# PP3_ptC_Alim.net
KiCad netlist of a schematic drawn in Altium Designer
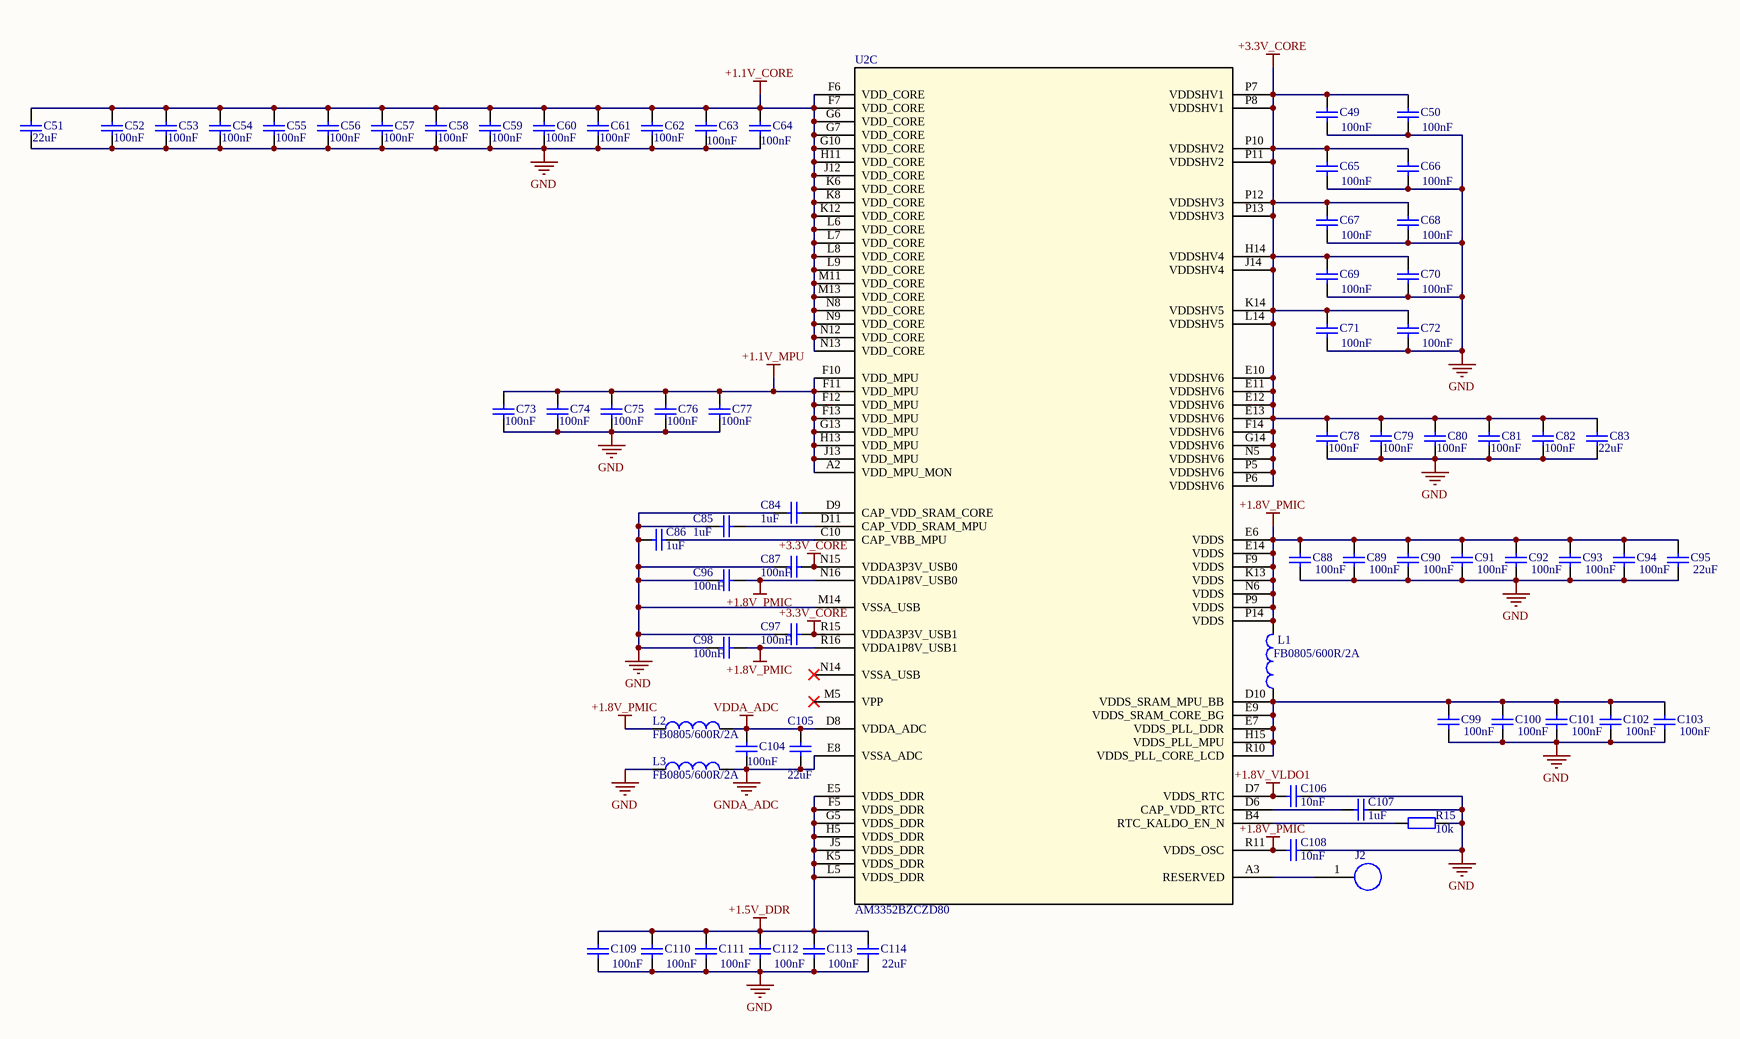
[diagram p0: PP3_ptC_Alim.SchDoc]

(export (version "E")
  (design (tool "Eeschema 10.0.6"))
  (components
    (comp (ref "C49")
      (value "100nF")
      (footprint "CAPC1005X05 (0402)")
      (description "Capacitor")
      (fields (field (name "Comment") "Cap 100nF"))
      (libsource (lib "Michel") (part "Cap"))
    )
    (comp (ref "C50")
      (value "100nF")
      (footprint "CAPC1005X05 (0402)")
      (description "Capacitor")
      (fields (field (name "Comment") "Cap 100nF"))
      (libsource (lib "Michel") (part "Cap"))
    )
    (comp (ref "C51")
      (value "22uF")
      (footprint "0805 (2012 metric)")
      (description "Capacitor")
      (fields (field (name "Comment") "Cap 22uF"))
      (libsource (lib "Michel") (part "Cap"))
    )
    (comp (ref "C52")
      (value "100nF")
      (footprint "CAPC1005X05 (0402)")
      (description "Capacitor")
      (fields (field (name "Comment") "Cap 100nF"))
      (libsource (lib "Michel") (part "Cap"))
    )
    (comp (ref "C53")
      (value "100nF")
      (footprint "CAPC1005X05 (0402)")
      (description "Capacitor")
      (fields (field (name "Comment") "Cap 100nF"))
      (libsource (lib "Michel") (part "Cap"))
    )
    (comp (ref "C54")
      (value "100nF")
      (footprint "CAPC1005X05 (0402)")
      (description "Capacitor")
      (fields (field (name "Comment") "Cap 100nF"))
      (libsource (lib "Michel") (part "Cap"))
    )
    (comp (ref "C55")
      (value "100nF")
      (footprint "CAPC1005X05 (0402)")
      (description "Capacitor")
      (fields (field (name "Comment") "Cap 100nF"))
      (libsource (lib "Michel") (part "Cap"))
    )
    (comp (ref "C56")
      (value "100nF")
      (footprint "CAPC1005X05 (0402)")
      (description "Capacitor")
      (fields (field (name "Comment") "Cap 100nF"))
      (libsource (lib "Michel") (part "Cap"))
    )
    (comp (ref "C57")
      (value "100nF")
      (footprint "CAPC1005X05 (0402)")
      (description "Capacitor")
      (fields (field (name "Comment") "Cap 100nF"))
      (libsource (lib "Michel") (part "Cap"))
    )
    (comp (ref "C58")
      (value "100nF")
      (footprint "CAPC1005X05 (0402)")
      (description "Capacitor")
      (fields (field (name "Comment") "Cap 100nF"))
      (libsource (lib "Michel") (part "Cap"))
    )
    (comp (ref "C59")
      (value "100nF")
      (footprint "CAPC1005X05 (0402)")
      (description "Capacitor")
      (fields (field (name "Comment") "Cap 100nF"))
      (libsource (lib "Michel") (part "Cap"))
    )
    (comp (ref "C60")
      (value "100nF")
      (footprint "CAPC1005X05 (0402)")
      (description "Capacitor")
      (fields (field (name "Comment") "Cap 100nF"))
      (libsource (lib "Michel") (part "Cap"))
    )
    (comp (ref "C61")
      (value "100nF")
      (footprint "CAPC1005X05 (0402)")
      (description "Capacitor")
      (fields (field (name "Comment") "Cap 100nF"))
      (libsource (lib "Michel") (part "Cap"))
    )
    (comp (ref "C62")
      (value "100nF")
      (footprint "CAPC1005X05 (0402)")
      (description "Capacitor")
      (fields (field (name "Comment") "Cap 100nF"))
      (libsource (lib "Michel") (part "Cap"))
    )
    (comp (ref "C63")
      (value "100nF")
      (footprint "CAPC1005X05 (0402)")
      (description "Capacitor")
      (fields (field (name "Comment") "Cap 100nF"))
      (libsource (lib "Michel") (part "Cap"))
    )
    (comp (ref "C64")
      (value "100nF")
      (footprint "CAPC1005X05 (0402)")
      (description "Capacitor")
      (fields (field (name "Comment") "Cap 100nF"))
      (libsource (lib "Michel") (part "Cap"))
    )
    (comp (ref "C65")
      (value "100nF")
      (footprint "CAPC1005X05 (0402)")
      (description "Capacitor")
      (fields (field (name "Comment") "Cap 100nF"))
      (libsource (lib "Michel") (part "Cap"))
    )
    (comp (ref "C66")
      (value "100nF")
      (footprint "CAPC1005X05 (0402)")
      (description "Capacitor")
      (fields (field (name "Comment") "Cap 100nF"))
      (libsource (lib "Michel") (part "Cap"))
    )
    (comp (ref "C67")
      (value "100nF")
      (footprint "CAPC1005X05 (0402)")
      (description "Capacitor")
      (fields (field (name "Comment") "Cap 100nF"))
      (libsource (lib "Michel") (part "Cap"))
    )
    (comp (ref "C68")
      (value "100nF")
      (footprint "CAPC1005X05 (0402)")
      (description "Capacitor")
      (fields (field (name "Comment") "Cap 100nF"))
      (libsource (lib "Michel") (part "Cap"))
    )
    (comp (ref "C69")
      (value "100nF")
      (footprint "CAPC1005X05 (0402)")
      (description "Capacitor")
      (fields (field (name "Comment") "Cap 100nF"))
      (libsource (lib "Michel") (part "Cap"))
    )
    (comp (ref "C70")
      (value "100nF")
      (footprint "CAPC1005X05 (0402)")
      (description "Capacitor")
      (fields (field (name "Comment") "Cap 100nF"))
      (libsource (lib "Michel") (part "Cap"))
    )
    (comp (ref "C71")
      (value "100nF")
      (footprint "CAPC1005X05 (0402)")
      (description "Capacitor")
      (fields (field (name "Comment") "Cap 100nF"))
      (libsource (lib "Michel") (part "Cap"))
    )
    (comp (ref "C72")
      (value "100nF")
      (footprint "CAPC1005X05 (0402)")
      (description "Capacitor")
      (fields (field (name "Comment") "Cap 100nF"))
      (libsource (lib "Michel") (part "Cap"))
    )
    (comp (ref "C73")
      (value "100nF")
      (footprint "CAPC1005X05 (0402)")
      (description "Capacitor")
      (fields (field (name "Comment") "Cap 100nF"))
      (libsource (lib "Michel") (part "Cap"))
    )
    (comp (ref "C74")
      (value "100nF")
      (footprint "CAPC1005X05 (0402)")
      (description "Capacitor")
      (fields (field (name "Comment") "Cap 100nF"))
      (libsource (lib "Michel") (part "Cap"))
    )
    (comp (ref "C75")
      (value "100nF")
      (footprint "CAPC1005X05 (0402)")
      (description "Capacitor")
      (fields (field (name "Comment") "Cap 100nF"))
      (libsource (lib "Michel") (part "Cap"))
    )
    (comp (ref "C76")
      (value "100nF")
      (footprint "CAPC1005X05 (0402)")
      (description "Capacitor")
      (fields (field (name "Comment") "Cap 100nF"))
      (libsource (lib "Michel") (part "Cap"))
    )
    (comp (ref "C77")
      (value "100nF")
      (footprint "CAPC1005X05 (0402)")
      (description "Capacitor")
      (fields (field (name "Comment") "Cap 100nF"))
      (libsource (lib "Michel") (part "Cap"))
    )
    (comp (ref "C78")
      (value "100nF")
      (footprint "CAPC1005X05 (0402)")
      (description "Capacitor")
      (fields (field (name "Comment") "Cap 100nF"))
      (libsource (lib "Michel") (part "Cap"))
    )
    (comp (ref "C79")
      (value "100nF")
      (footprint "CAPC1005X05 (0402)")
      (description "Capacitor")
      (fields (field (name "Comment") "Cap 100nF"))
      (libsource (lib "Michel") (part "Cap"))
    )
    (comp (ref "C80")
      (value "100nF")
      (footprint "CAPC1005X05 (0402)")
      (description "Capacitor")
      (fields (field (name "Comment") "Cap 100nF"))
      (libsource (lib "Michel") (part "Cap"))
    )
    (comp (ref "C81")
      (value "100nF")
      (footprint "CAPC1005X05 (0402)")
      (description "Capacitor")
      (fields (field (name "Comment") "Cap 100nF"))
      (libsource (lib "Michel") (part "Cap"))
    )
    (comp (ref "C82")
      (value "100nF")
      (footprint "CAPC1005X05 (0402)")
      (description "Capacitor")
      (fields (field (name "Comment") "Cap 100nF"))
      (libsource (lib "Michel") (part "Cap"))
    )
    (comp (ref "C83")
      (value "22uF")
      (footprint "0805 (2012 metric)")
      (description "Capacitor")
      (fields (field (name "Comment") "Cap 22uF"))
      (libsource (lib "Michel") (part "Cap"))
    )
    (comp (ref "C84")
      (value "1uF")
      (footprint "CAPC1608X08")
      (description "Capacitor")
      (fields (field (name "Comment") "Cap 1uF"))
      (libsource (lib "Michel") (part "Cap"))
    )
    (comp (ref "C85")
      (value "1uF")
      (footprint "CAPC1608X08")
      (description "Capacitor")
      (fields (field (name "Comment") "Cap 1uF"))
      (libsource (lib "Michel") (part "Cap"))
    )
    (comp (ref "C86")
      (value "1uF")
      (footprint "CAPC1608X08")
      (description "Capacitor")
      (fields (field (name "Comment") "Cap 1uF"))
      (libsource (lib "Michel") (part "Cap"))
    )
    (comp (ref "C87")
      (value "100nF")
      (footprint "CAPC1005X05 (0402)")
      (description "Capacitor")
      (fields (field (name "Comment") "Cap 100nF"))
      (libsource (lib "Michel") (part "Cap"))
    )
    (comp (ref "C88")
      (value "100nF")
      (footprint "CAPC1005X05 (0402)")
      (description "Capacitor")
      (fields (field (name "Comment") "Cap 100nF"))
      (libsource (lib "Michel") (part "Cap"))
    )
    (comp (ref "C89")
      (value "100nF")
      (footprint "CAPC1005X05 (0402)")
      (description "Capacitor")
      (fields (field (name "Comment") "Cap 100nF"))
      (libsource (lib "Michel") (part "Cap"))
    )
    (comp (ref "C90")
      (value "100nF")
      (footprint "CAPC1005X05 (0402)")
      (description "Capacitor")
      (fields (field (name "Comment") "Cap 100nF"))
      (libsource (lib "Michel") (part "Cap"))
    )
    (comp (ref "C91")
      (value "100nF")
      (footprint "CAPC1005X05 (0402)")
      (description "Capacitor")
      (fields (field (name "Comment") "Cap 100nF"))
      (libsource (lib "Michel") (part "Cap"))
    )
    (comp (ref "C92")
      (value "100nF")
      (footprint "CAPC1005X05 (0402)")
      (description "Capacitor")
      (fields (field (name "Comment") "Cap 100nF"))
      (libsource (lib "Michel") (part "Cap"))
    )
    (comp (ref "C93")
      (value "100nF")
      (footprint "CAPC1005X05 (0402)")
      (description "Capacitor")
      (fields (field (name "Comment") "Cap 100nF"))
      (libsource (lib "Michel") (part "Cap"))
    )
    (comp (ref "C94")
      (value "100nF")
      (footprint "CAPC1005X05 (0402)")
      (description "Capacitor")
      (fields (field (name "Comment") "Cap 100nF"))
      (libsource (lib "Michel") (part "Cap"))
    )
    (comp (ref "C95")
      (value "22uF")
      (footprint "0805 (2012 metric)")
      (description "Capacitor")
      (fields (field (name "Comment") "Cap 22uF"))
      (libsource (lib "Michel") (part "Cap"))
    )
    (comp (ref "C96")
      (value "100nF")
      (footprint "CAPC1005X05 (0402)")
      (description "Capacitor")
      (fields (field (name "Comment") "Cap 100nF"))
      (libsource (lib "Michel") (part "Cap"))
    )
    (comp (ref "C97")
      (value "100nF")
      (footprint "CAPC1005X05 (0402)")
      (description "Capacitor")
      (fields (field (name "Comment") "Cap 100nF"))
      (libsource (lib "Michel") (part "Cap"))
    )
    (comp (ref "C98")
      (value "100nF")
      (footprint "CAPC1005X05 (0402)")
      (description "Capacitor")
      (fields (field (name "Comment") "Cap 100nF"))
      (libsource (lib "Michel") (part "Cap"))
    )
    (comp (ref "C99")
      (value "100nF")
      (footprint "CAPC1005X05 (0402)")
      (description "Capacitor")
      (fields (field (name "Comment") "Cap 100nF"))
      (libsource (lib "Michel") (part "Cap"))
    )
    (comp (ref "C100")
      (value "100nF")
      (footprint "CAPC1005X05 (0402)")
      (description "Capacitor")
      (fields (field (name "Comment") "Cap 100nF"))
      (libsource (lib "Michel") (part "Cap"))
    )
    (comp (ref "C101")
      (value "100nF")
      (footprint "CAPC1005X05 (0402)")
      (description "Capacitor")
      (fields (field (name "Comment") "Cap 100nF"))
      (libsource (lib "Michel") (part "Cap"))
    )
    (comp (ref "C102")
      (value "100nF")
      (footprint "CAPC1005X05 (0402)")
      (description "Capacitor")
      (fields (field (name "Comment") "Cap 100nF"))
      (libsource (lib "Michel") (part "Cap"))
    )
    (comp (ref "C103")
      (value "100nF")
      (footprint "CAPC1005X05 (0402)")
      (description "Capacitor")
      (fields (field (name "Comment") "Cap 100nF"))
      (libsource (lib "Michel") (part "Cap"))
    )
    (comp (ref "C104")
      (value "100nF")
      (footprint "CAPC1005X05 (0402)")
      (description "Capacitor")
      (fields (field (name "Comment") "Cap 100nF"))
      (libsource (lib "Michel") (part "Cap"))
    )
    (comp (ref "C105")
      (value "22uF")
      (footprint "0805 (2012 metric)")
      (description "Capacitor")
      (fields (field (name "Comment") "Cap 22uF"))
      (libsource (lib "Michel") (part "Cap"))
    )
    (comp (ref "C106")
      (value "10nF")
      (footprint "CAPC1005X05 (0402)")
      (description "Capacitor")
      (fields (field (name "Comment") "Cap 10uF"))
      (libsource (lib "Michel") (part "Cap"))
    )
    (comp (ref "C107")
      (value "1uF")
      (footprint "CAPC1608X08")
      (description "Capacitor")
      (fields (field (name "Comment") "Cap 1uF"))
      (libsource (lib "Michel") (part "Cap"))
    )
    (comp (ref "C108")
      (value "10nF")
      (footprint "CAPC1005X05 (0402)")
      (description "Capacitor")
      (fields (field (name "Comment") "Cap 10uF"))
      (libsource (lib "Michel") (part "Cap"))
    )
    (comp (ref "C109")
      (value "100nF")
      (footprint "CAPC1005X05 (0402)")
      (description "Capacitor")
      (fields (field (name "Comment") "Cap 100nF"))
      (libsource (lib "Michel") (part "Cap"))
    )
    (comp (ref "C110")
      (value "100nF")
      (footprint "CAPC1005X05 (0402)")
      (description "Capacitor")
      (fields (field (name "Comment") "Cap 100nF"))
      (libsource (lib "Michel") (part "Cap"))
    )
    (comp (ref "C111")
      (value "100nF")
      (footprint "CAPC1005X05 (0402)")
      (description "Capacitor")
      (fields (field (name "Comment") "Cap 100nF"))
      (libsource (lib "Michel") (part "Cap"))
    )
    (comp (ref "C112")
      (value "100nF")
      (footprint "CAPC1005X05 (0402)")
      (description "Capacitor")
      (fields (field (name "Comment") "Cap 100nF"))
      (libsource (lib "Michel") (part "Cap"))
    )
    (comp (ref "C113")
      (value "100nF")
      (footprint "CAPC1005X05 (0402)")
      (description "Capacitor")
      (fields (field (name "Comment") "Cap 100nF"))
      (libsource (lib "Michel") (part "Cap"))
    )
    (comp (ref "C114")
      (value "22uF")
      (footprint "0805 (2012 metric)")
      (description "Capacitor")
      (fields (field (name "Comment") "Cap 22uF"))
      (libsource (lib "Michel") (part "Cap"))
    )
    (comp (ref "J2") (value "Pad traversant") (footprint "Pad") (libsource (lib "Michel") (part "Pad")))
    (comp (ref "L1")
      (value "FB0805/600R/2A")
      (footprint "IND2012X8")
      (libsource (lib "Michel") (part "Inductor"))
    )
    (comp (ref "L2")
      (value "FB0805/600R/2A")
      (footprint "IND2012X8")
      (libsource (lib "Michel") (part "Inductor"))
    )
    (comp (ref "L3")
      (value "FB0805/600R/2A")
      (footprint "IND2012X8")
      (libsource (lib "Michel") (part "Inductor"))
    )
    (comp (ref "R15")
      (value "10k")
      (footprint "RESC1608X05")
      (description "Resistor")
      (fields (field (name "Comment") "Res 10k"))
      (libsource (lib "Michel") (part "Res2"))
    )
    (comp (ref "U2")
      (value "AM3352BZCZD80")
      (footprint "ZCZ324")
      (description "Microprocesseur ARM")
      (libsource (lib "Michel") (part "AM3352BZCZD80"))
    )
  )
  (nets
    (net (code "1") (name "+1.1V_CORE") (class "Default")
      (node (ref "C51") (pin "2") (pinfunction "2_2") (pintype "passive"))
      (node (ref "C52") (pin "1") (pinfunction "1_1") (pintype "passive"))
      (node (ref "C53") (pin "1") (pinfunction "1_1") (pintype "passive"))
      (node (ref "C54") (pin "1") (pinfunction "1_1") (pintype "passive"))
      (node (ref "C55") (pin "1") (pinfunction "1_1") (pintype "passive"))
      (node (ref "C56") (pin "1") (pinfunction "1_1") (pintype "passive"))
      (node (ref "C57") (pin "1") (pinfunction "1_1") (pintype "passive"))
      (node (ref "C58") (pin "1") (pinfunction "1_1") (pintype "passive"))
      (node (ref "C59") (pin "1") (pinfunction "1_1") (pintype "passive"))
      (node (ref "C60") (pin "1") (pinfunction "1_1") (pintype "passive"))
      (node (ref "C61") (pin "1") (pinfunction "1_1") (pintype "passive"))
      (node (ref "C62") (pin "1") (pinfunction "1_1") (pintype "passive"))
      (node (ref "C63") (pin "1") (pinfunction "1_1") (pintype "passive"))
      (node (ref "C64") (pin "1") (pinfunction "1_1") (pintype "passive"))
      (node (ref "U2") (pin "F6") (pinfunction "VDD_CORE_F6") (pintype "power_in"))
      (node (ref "U2") (pin "F7") (pinfunction "VDD_CORE_F7") (pintype "power_in"))
      (node (ref "U2") (pin "G10") (pinfunction "VDD_CORE_G10") (pintype "power_in"))
      (node (ref "U2") (pin "G6") (pinfunction "VDD_CORE_G6") (pintype "power_in"))
      (node (ref "U2") (pin "G7") (pinfunction "VDD_CORE_G7") (pintype "power_in"))
      (node (ref "U2") (pin "H11") (pinfunction "VDD_CORE_H11") (pintype "power_in"))
      (node (ref "U2") (pin "J12") (pinfunction "VDD_CORE_J12") (pintype "power_in"))
      (node (ref "U2") (pin "K12") (pinfunction "VDD_CORE_K12") (pintype "power_in"))
      (node (ref "U2") (pin "K6") (pinfunction "VDD_CORE_K6") (pintype "power_in"))
      (node (ref "U2") (pin "K8") (pinfunction "VDD_CORE_K8") (pintype "power_in"))
      (node (ref "U2") (pin "L6") (pinfunction "VDD_CORE_L6") (pintype "power_in"))
      (node (ref "U2") (pin "L7") (pinfunction "VDD_CORE_L7") (pintype "power_in"))
      (node (ref "U2") (pin "L8") (pinfunction "VDD_CORE_L8") (pintype "power_in"))
      (node (ref "U2") (pin "L9") (pinfunction "VDD_CORE_L9") (pintype "power_in"))
      (node (ref "U2") (pin "M11") (pinfunction "VDD_CORE_M11") (pintype "power_in"))
      (node (ref "U2") (pin "M13") (pinfunction "VDD_CORE_M13") (pintype "power_in"))
      (node (ref "U2") (pin "N12") (pinfunction "VDD_CORE_N12") (pintype "power_in"))
      (node (ref "U2") (pin "N13") (pinfunction "VDD_CORE_N13") (pintype "power_in"))
      (node (ref "U2") (pin "N8") (pinfunction "VDD_CORE_N8") (pintype "power_in"))
      (node (ref "U2") (pin "N9") (pinfunction "VDD_CORE_N9") (pintype "power_in"))
    )
    (net (code "2") (name "+1.1V_MPU") (class "Default")
      (node (ref "C73") (pin "1") (pinfunction "1_1") (pintype "passive"))
      (node (ref "C74") (pin "1") (pinfunction "1_1") (pintype "passive"))
      (node (ref "C75") (pin "1") (pinfunction "1_1") (pintype "passive"))
      (node (ref "C76") (pin "1") (pinfunction "1_1") (pintype "passive"))
      (node (ref "C77") (pin "1") (pinfunction "1_1") (pintype "passive"))
      (node (ref "U2") (pin "A2") (pinfunction "VDD_MPU_MON_A2") (pintype "power_in"))
      (node (ref "U2") (pin "F10") (pinfunction "VDD_MPU_F10") (pintype "power_in"))
      (node (ref "U2") (pin "F11") (pinfunction "VDD_MPU_F11") (pintype "power_in"))
      (node (ref "U2") (pin "F12") (pinfunction "VDD_MPU_F12") (pintype "power_in"))
      (node (ref "U2") (pin "F13") (pinfunction "VDD_MPU_F13") (pintype "power_in"))
      (node (ref "U2") (pin "G13") (pinfunction "VDD_MPU_G13") (pintype "power_in"))
      (node (ref "U2") (pin "H13") (pinfunction "VDD_MPU_H13") (pintype "power_in"))
      (node (ref "U2") (pin "J13") (pinfunction "VDD_MPU_J13") (pintype "power_in"))
    )
    (net (code "3") (name "+1.5V_DDR") (class "Default")
      (node (ref "C109") (pin "1") (pinfunction "1_1") (pintype "passive"))
      (node (ref "C110") (pin "1") (pinfunction "1_1") (pintype "passive"))
      (node (ref "C111") (pin "1") (pinfunction "1_1") (pintype "passive"))
      (node (ref "C112") (pin "1") (pinfunction "1_1") (pintype "passive"))
      (node (ref "C113") (pin "1") (pinfunction "1_1") (pintype "passive"))
      (node (ref "C114") (pin "2") (pinfunction "2_2") (pintype "passive"))
      (node (ref "U2") (pin "E5") (pinfunction "VDDS_DDR_E5") (pintype "power_in"))
      (node (ref "U2") (pin "F5") (pinfunction "VDDS_DDR_F5") (pintype "power_in"))
      (node (ref "U2") (pin "G5") (pinfunction "VDDS_DDR_G5") (pintype "power_in"))
      (node (ref "U2") (pin "H5") (pinfunction "VDDS_DDR_H5") (pintype "power_in"))
      (node (ref "U2") (pin "J5") (pinfunction "VDDS_DDR_J5") (pintype "power_in"))
      (node (ref "U2") (pin "K5") (pinfunction "VDDS_DDR_K5") (pintype "power_in"))
      (node (ref "U2") (pin "L5") (pinfunction "VDDS_DDR_L5") (pintype "power_in"))
    )
    (net (code "4") (name "+1.8V_PMIC") (class "Default")
      (node (ref "C108") (pin "2") (pinfunction "2_2") (pintype "passive"))
      (node (ref "C88") (pin "1") (pinfunction "1_1") (pintype "passive"))
      (node (ref "C89") (pin "1") (pinfunction "1_1") (pintype "passive"))
      (node (ref "C90") (pin "1") (pinfunction "1_1") (pintype "passive"))
      (node (ref "C91") (pin "1") (pinfunction "1_1") (pintype "passive"))
      (node (ref "C92") (pin "1") (pinfunction "1_1") (pintype "passive"))
      (node (ref "C93") (pin "1") (pinfunction "1_1") (pintype "passive"))
      (node (ref "C94") (pin "1") (pinfunction "1_1") (pintype "passive"))
      (node (ref "C95") (pin "2") (pinfunction "2_2") (pintype "passive"))
      (node (ref "C96") (pin "2") (pinfunction "2_2") (pintype "passive"))
      (node (ref "C98") (pin "2") (pinfunction "2_2") (pintype "passive"))
      (node (ref "L1") (pin "2") (pinfunction "2_2") (pintype "passive"))
      (node (ref "L2") (pin "1") (pinfunction "1_1") (pintype "passive"))
      (node (ref "U2") (pin "E14") (pinfunction "VDDS_E14") (pintype "power_in"))
      (node (ref "U2") (pin "E6") (pinfunction "VDDS_E6") (pintype "power_in"))
      (node (ref "U2") (pin "F9") (pinfunction "VDDS_F9") (pintype "power_in"))
      (node (ref "U2") (pin "K13") (pinfunction "VDDS_K13") (pintype "power_in"))
      (node (ref "U2") (pin "N16") (pinfunction "VDDA1P8V_USB0_N16") (pintype "power_in"))
      (node (ref "U2") (pin "N6") (pinfunction "VDDS_N6") (pintype "power_in"))
      (node (ref "U2") (pin "P14") (pinfunction "VDDS_P14") (pintype "power_in"))
      (node (ref "U2") (pin "P9") (pinfunction "VDDS_P9") (pintype "power_in"))
      (node (ref "U2") (pin "R11") (pinfunction "VDDS_OSC_R11") (pintype "power_in"))
      (node (ref "U2") (pin "R16") (pinfunction "VDDA1P8V_USB1_R16") (pintype "power_in"))
    )
    (net (code "5") (name "+1.8V_VLDO1") (class "Default")
      (node (ref "C106") (pin "2") (pinfunction "2_2") (pintype "passive"))
      (node (ref "U2") (pin "D7") (pinfunction "VDDS_RTC_D7") (pintype "power_in"))
    )
    (net (code "6") (name "+3.3V_CORE") (class "Default")
      (node (ref "C49") (pin "1") (pinfunction "1_1") (pintype "passive"))
      (node (ref "C50") (pin "1") (pinfunction "1_1") (pintype "passive"))
      (node (ref "C65") (pin "1") (pinfunction "1_1") (pintype "passive"))
      (node (ref "C66") (pin "1") (pinfunction "1_1") (pintype "passive"))
      (node (ref "C67") (pin "1") (pinfunction "1_1") (pintype "passive"))
      (node (ref "C68") (pin "1") (pinfunction "1_1") (pintype "passive"))
      (node (ref "C69") (pin "1") (pinfunction "1_1") (pintype "passive"))
      (node (ref "C70") (pin "1") (pinfunction "1_1") (pintype "passive"))
      (node (ref "C71") (pin "1") (pinfunction "1_1") (pintype "passive"))
      (node (ref "C72") (pin "1") (pinfunction "1_1") (pintype "passive"))
      (node (ref "C78") (pin "1") (pinfunction "1_1") (pintype "passive"))
      (node (ref "C79") (pin "1") (pinfunction "1_1") (pintype "passive"))
      (node (ref "C80") (pin "1") (pinfunction "1_1") (pintype "passive"))
      (node (ref "C81") (pin "1") (pinfunction "1_1") (pintype "passive"))
      (node (ref "C82") (pin "1") (pinfunction "1_1") (pintype "passive"))
      (node (ref "C83") (pin "2") (pinfunction "2_2") (pintype "passive"))
      (node (ref "C87") (pin "2") (pinfunction "2_2") (pintype "passive"))
      (node (ref "C97") (pin "2") (pinfunction "2_2") (pintype "passive"))
      (node (ref "U2") (pin "E10") (pinfunction "VDDSHV6_E10") (pintype "power_in"))
      (node (ref "U2") (pin "E11") (pinfunction "VDDSHV6_E11") (pintype "power_in"))
      (node (ref "U2") (pin "E12") (pinfunction "VDDSHV6_E12") (pintype "power_in"))
      (node (ref "U2") (pin "E13") (pinfunction "VDDSHV6_E13") (pintype "power_in"))
      (node (ref "U2") (pin "F14") (pinfunction "VDDSHV6_F14") (pintype "power_in"))
      (node (ref "U2") (pin "G14") (pinfunction "VDDSHV6_G14") (pintype "power_in"))
      (node (ref "U2") (pin "H14") (pinfunction "VDDSHV4_H14") (pintype "power_in"))
      (node (ref "U2") (pin "J14") (pinfunction "VDDSHV4_J14") (pintype "power_in"))
      (node (ref "U2") (pin "K14") (pinfunction "VDDSHV5_K14") (pintype "power_in"))
      (node (ref "U2") (pin "L14") (pinfunction "VDDSHV5_L14") (pintype "power_in"))
      (node (ref "U2") (pin "N15") (pinfunction "VDDA3P3V_USB0_N15") (pintype "power_in"))
      (node (ref "U2") (pin "N5") (pinfunction "VDDSHV6_N5") (pintype "power_in"))
      (node (ref "U2") (pin "P10") (pinfunction "VDDSHV2_P10") (pintype "power_in"))
      (node (ref "U2") (pin "P11") (pinfunction "VDDSHV2_P11") (pintype "power_in"))
      (node (ref "U2") (pin "P12") (pinfunction "VDDSHV3_P12") (pintype "power_in"))
      (node (ref "U2") (pin "P13") (pinfunction "VDDSHV3_P13") (pintype "power_in"))
      (node (ref "U2") (pin "P5") (pinfunction "VDDSHV6_P5") (pintype "power_in"))
      (node (ref "U2") (pin "P6") (pinfunction "VDDSHV6_P6") (pintype "power_in"))
      (node (ref "U2") (pin "P7") (pinfunction "VDDSHV1_P7") (pintype "power_in"))
      (node (ref "U2") (pin "P8") (pinfunction "VDDSHV1_P8") (pintype "power_in"))
      (node (ref "U2") (pin "R15") (pinfunction "VDDA3P3V_USB1_R15") (pintype "power_in"))
    )
    (net (code "7") (name "GND") (class "Default")
      (node (ref "C100") (pin "2") (pinfunction "2_2") (pintype "passive"))
      (node (ref "C101") (pin "2") (pinfunction "2_2") (pintype "passive"))
      (node (ref "C102") (pin "2") (pinfunction "2_2") (pintype "passive"))
      (node (ref "C103") (pin "2") (pinfunction "2_2") (pintype "passive"))
      (node (ref "C106") (pin "1") (pinfunction "1_1") (pintype "passive"))
      (node (ref "C107") (pin "2") (pinfunction "2_2") (pintype "passive"))
      (node (ref "C108") (pin "1") (pinfunction "1_1") (pintype "passive"))
      (node (ref "C109") (pin "2") (pinfunction "2_2") (pintype "passive"))
      (node (ref "C110") (pin "2") (pinfunction "2_2") (pintype "passive"))
      (node (ref "C111") (pin "2") (pinfunction "2_2") (pintype "passive"))
      (node (ref "C112") (pin "2") (pinfunction "2_2") (pintype "passive"))
      (node (ref "C113") (pin "2") (pinfunction "2_2") (pintype "passive"))
      (node (ref "C114") (pin "1") (pinfunction "1_1") (pintype "passive"))
      (node (ref "C49") (pin "2") (pinfunction "2_2") (pintype "passive"))
      (node (ref "C50") (pin "2") (pinfunction "2_2") (pintype "passive"))
      (node (ref "C51") (pin "1") (pinfunction "1_1") (pintype "passive"))
      (node (ref "C52") (pin "2") (pinfunction "2_2") (pintype "passive"))
      (node (ref "C53") (pin "2") (pinfunction "2_2") (pintype "passive"))
      (node (ref "C54") (pin "2") (pinfunction "2_2") (pintype "passive"))
      (node (ref "C55") (pin "2") (pinfunction "2_2") (pintype "passive"))
      (node (ref "C56") (pin "2") (pinfunction "2_2") (pintype "passive"))
      (node (ref "C57") (pin "2") (pinfunction "2_2") (pintype "passive"))
      (node (ref "C58") (pin "2") (pinfunction "2_2") (pintype "passive"))
      (node (ref "C59") (pin "2") (pinfunction "2_2") (pintype "passive"))
      (node (ref "C60") (pin "2") (pinfunction "2_2") (pintype "passive"))
      (node (ref "C61") (pin "2") (pinfunction "2_2") (pintype "passive"))
      (node (ref "C62") (pin "2") (pinfunction "2_2") (pintype "passive"))
      (node (ref "C63") (pin "2") (pinfunction "2_2") (pintype "passive"))
      (node (ref "C64") (pin "2") (pinfunction "2_2") (pintype "passive"))
      (node (ref "C65") (pin "2") (pinfunction "2_2") (pintype "passive"))
      (node (ref "C66") (pin "2") (pinfunction "2_2") (pintype "passive"))
      (node (ref "C67") (pin "2") (pinfunction "2_2") (pintype "passive"))
      (node (ref "C68") (pin "2") (pinfunction "2_2") (pintype "passive"))
      (node (ref "C69") (pin "2") (pinfunction "2_2") (pintype "passive"))
      (node (ref "C70") (pin "2") (pinfunction "2_2") (pintype "passive"))
      (node (ref "C71") (pin "2") (pinfunction "2_2") (pintype "passive"))
      (node (ref "C72") (pin "2") (pinfunction "2_2") (pintype "passive"))
      (node (ref "C73") (pin "2") (pinfunction "2_2") (pintype "passive"))
      (node (ref "C74") (pin "2") (pinfunction "2_2") (pintype "passive"))
      (node (ref "C75") (pin "2") (pinfunction "2_2") (pintype "passive"))
      (node (ref "C76") (pin "2") (pinfunction "2_2") (pintype "passive"))
      (node (ref "C77") (pin "2") (pinfunction "2_2") (pintype "passive"))
      (node (ref "C78") (pin "2") (pinfunction "2_2") (pintype "passive"))
      (node (ref "C79") (pin "2") (pinfunction "2_2") (pintype "passive"))
      (node (ref "C80") (pin "2") (pinfunction "2_2") (pintype "passive"))
      (node (ref "C81") (pin "2") (pinfunction "2_2") (pintype "passive"))
      (node (ref "C82") (pin "2") (pinfunction "2_2") (pintype "passive"))
      (node (ref "C83") (pin "1") (pinfunction "1_1") (pintype "passive"))
      (node (ref "C84") (pin "1") (pinfunction "1_1") (pintype "passive"))
      (node (ref "C85") (pin "1") (pinfunction "1_1") (pintype "passive"))
      (node (ref "C86") (pin "1") (pinfunction "1_1") (pintype "passive"))
      (node (ref "C87") (pin "1") (pinfunction "1_1") (pintype "passive"))
      (node (ref "C88") (pin "2") (pinfunction "2_2") (pintype "passive"))
      (node (ref "C89") (pin "2") (pinfunction "2_2") (pintype "passive"))
      (node (ref "C90") (pin "2") (pinfunction "2_2") (pintype "passive"))
      (node (ref "C91") (pin "2") (pinfunction "2_2") (pintype "passive"))
      (node (ref "C92") (pin "2") (pinfunction "2_2") (pintype "passive"))
      (node (ref "C93") (pin "2") (pinfunction "2_2") (pintype "passive"))
      (node (ref "C94") (pin "2") (pinfunction "2_2") (pintype "passive"))
      (node (ref "C95") (pin "1") (pinfunction "1_1") (pintype "passive"))
      (node (ref "C96") (pin "1") (pinfunction "1_1") (pintype "passive"))
      (node (ref "C97") (pin "1") (pinfunction "1_1") (pintype "passive"))
      (node (ref "C98") (pin "1") (pinfunction "1_1") (pintype "passive"))
      (node (ref "C99") (pin "2") (pinfunction "2_2") (pintype "passive"))
      (node (ref "L3") (pin "1") (pinfunction "1_1") (pintype "passive"))
      (node (ref "R15") (pin "1") (pinfunction "1_1") (pintype "passive"))
      (node (ref "U2") (pin "M14") (pinfunction "VSSA_USB_M14") (pintype "power_in"))
    )
    (net (code "8") (name "GNDA_ADC") (class "Default")
      (node (ref "C104") (pin "2") (pinfunction "2_2") (pintype "passive"))
      (node (ref "C105") (pin "1") (pinfunction "1_1") (pintype "passive"))
      (node (ref "L3") (pin "2") (pinfunction "2_2") (pintype "passive"))
      (node (ref "U2") (pin "E8") (pinfunction "VSSA_ADC_E8") (pintype "power_in"))
    )
    (net (code "9") (name "Net-(J2-PAD)") (class "Default")
      (node (ref "J2") (pin "1") (pinfunction "PAD_1") (pintype "passive"))
      (node (ref "U2") (pin "A3") (pinfunction "RESERVED_A3") (pintype "passive"))
    )
    (net (code "10") (name "Net-(U2C-CAP_VBB_MPU)") (class "Default")
      (node (ref "C86") (pin "2") (pinfunction "2_2") (pintype "passive"))
      (node (ref "U2") (pin "C10") (pinfunction "CAP_VBB_MPU_C10") (pintype "passive"))
    )
    (net (code "11") (name "Net-(U2C-CAP_VDD_RTC)") (class "Default")
      (node (ref "C107") (pin "1") (pinfunction "1_1") (pintype "passive"))
      (node (ref "U2") (pin "D6") (pinfunction "CAP_VDD_RTC_D6") (pintype "passive"))
    )
    (net (code "12") (name "Net-(U2C-CAP_VDD_SRAM_CORE)") (class "Default")
      (node (ref "C84") (pin "2") (pinfunction "2_2") (pintype "passive"))
      (node (ref "U2") (pin "D9") (pinfunction "CAP_VDD_SRAM_CORE_D9") (pintype "passive"))
    )
    (net (code "13") (name "Net-(U2C-CAP_VDD_SRAM_MPU)") (class "Default")
      (node (ref "C85") (pin "2") (pinfunction "2_2") (pintype "passive"))
      (node (ref "U2") (pin "D11") (pinfunction "CAP_VDD_SRAM_MPU_D11") (pintype "passive"))
    )
    (net (code "14") (name "Net-(U2C-RTC_KALDO_EN_N)") (class "Default")
      (node (ref "R15") (pin "2") (pinfunction "2_2") (pintype "passive"))
      (node (ref "U2") (pin "B4") (pinfunction "RTC_KALDO_EN_N_B4") (pintype "passive"))
    )
    (net (code "15") (name "Net-(U2C-VDDS_PLL_CORE_LCD)") (class "Default")
      (node (ref "C100") (pin "1") (pinfunction "1_1") (pintype "passive"))
      (node (ref "C101") (pin "1") (pinfunction "1_1") (pintype "passive"))
      (node (ref "C102") (pin "1") (pinfunction "1_1") (pintype "passive"))
      (node (ref "C103") (pin "1") (pinfunction "1_1") (pintype "passive"))
      (node (ref "C99") (pin "1") (pinfunction "1_1") (pintype "passive"))
      (node (ref "L1") (pin "1") (pinfunction "1_1") (pintype "passive"))
      (node (ref "U2") (pin "D10") (pinfunction "VDDS_SRAM_MPU_BB_D10") (pintype "power_in"))
      (node (ref "U2") (pin "E7") (pinfunction "VDDS_PLL_DDR_E7") (pintype "power_in"))
      (node (ref "U2") (pin "E9") (pinfunction "VDDS_SRAM_CORE_BG_E9") (pintype "power_in"))
      (node (ref "U2") (pin "H15") (pinfunction "VDDS_PLL_MPU_H15") (pintype "power_in"))
      (node (ref "U2") (pin "R10") (pinfunction "VDDS_PLL_CORE_LCD_R10") (pintype "power_in"))
    )
    (net (code "16") (name "VDDA_ADC") (class "Default")
      (node (ref "C104") (pin "1") (pinfunction "1_1") (pintype "passive"))
      (node (ref "C105") (pin "2") (pinfunction "2_2") (pintype "passive"))
      (node (ref "L2") (pin "2") (pinfunction "2_2") (pintype "passive"))
      (node (ref "U2") (pin "D8") (pinfunction "VDDA_ADC_D8") (pintype "power_in"))
    )
    (net (code "17") (name "unconnected-(U2C-VPP-PadM5)") (class "Default")
      (node (ref "U2") (pin "M5") (pinfunction "VPP_M5") (pintype "power_in+no_connect"))
    )
    (net (code "18") (name "unconnected-(U2C-VSSA_USB-PadN14)") (class "Default")
      (node (ref "U2") (pin "N14") (pinfunction "VSSA_USB_N14") (pintype "power_in+no_connect"))
    )
  )
)
